# astable_555_timer.net
KiCad netlist of a schematic drawn in EAGLE
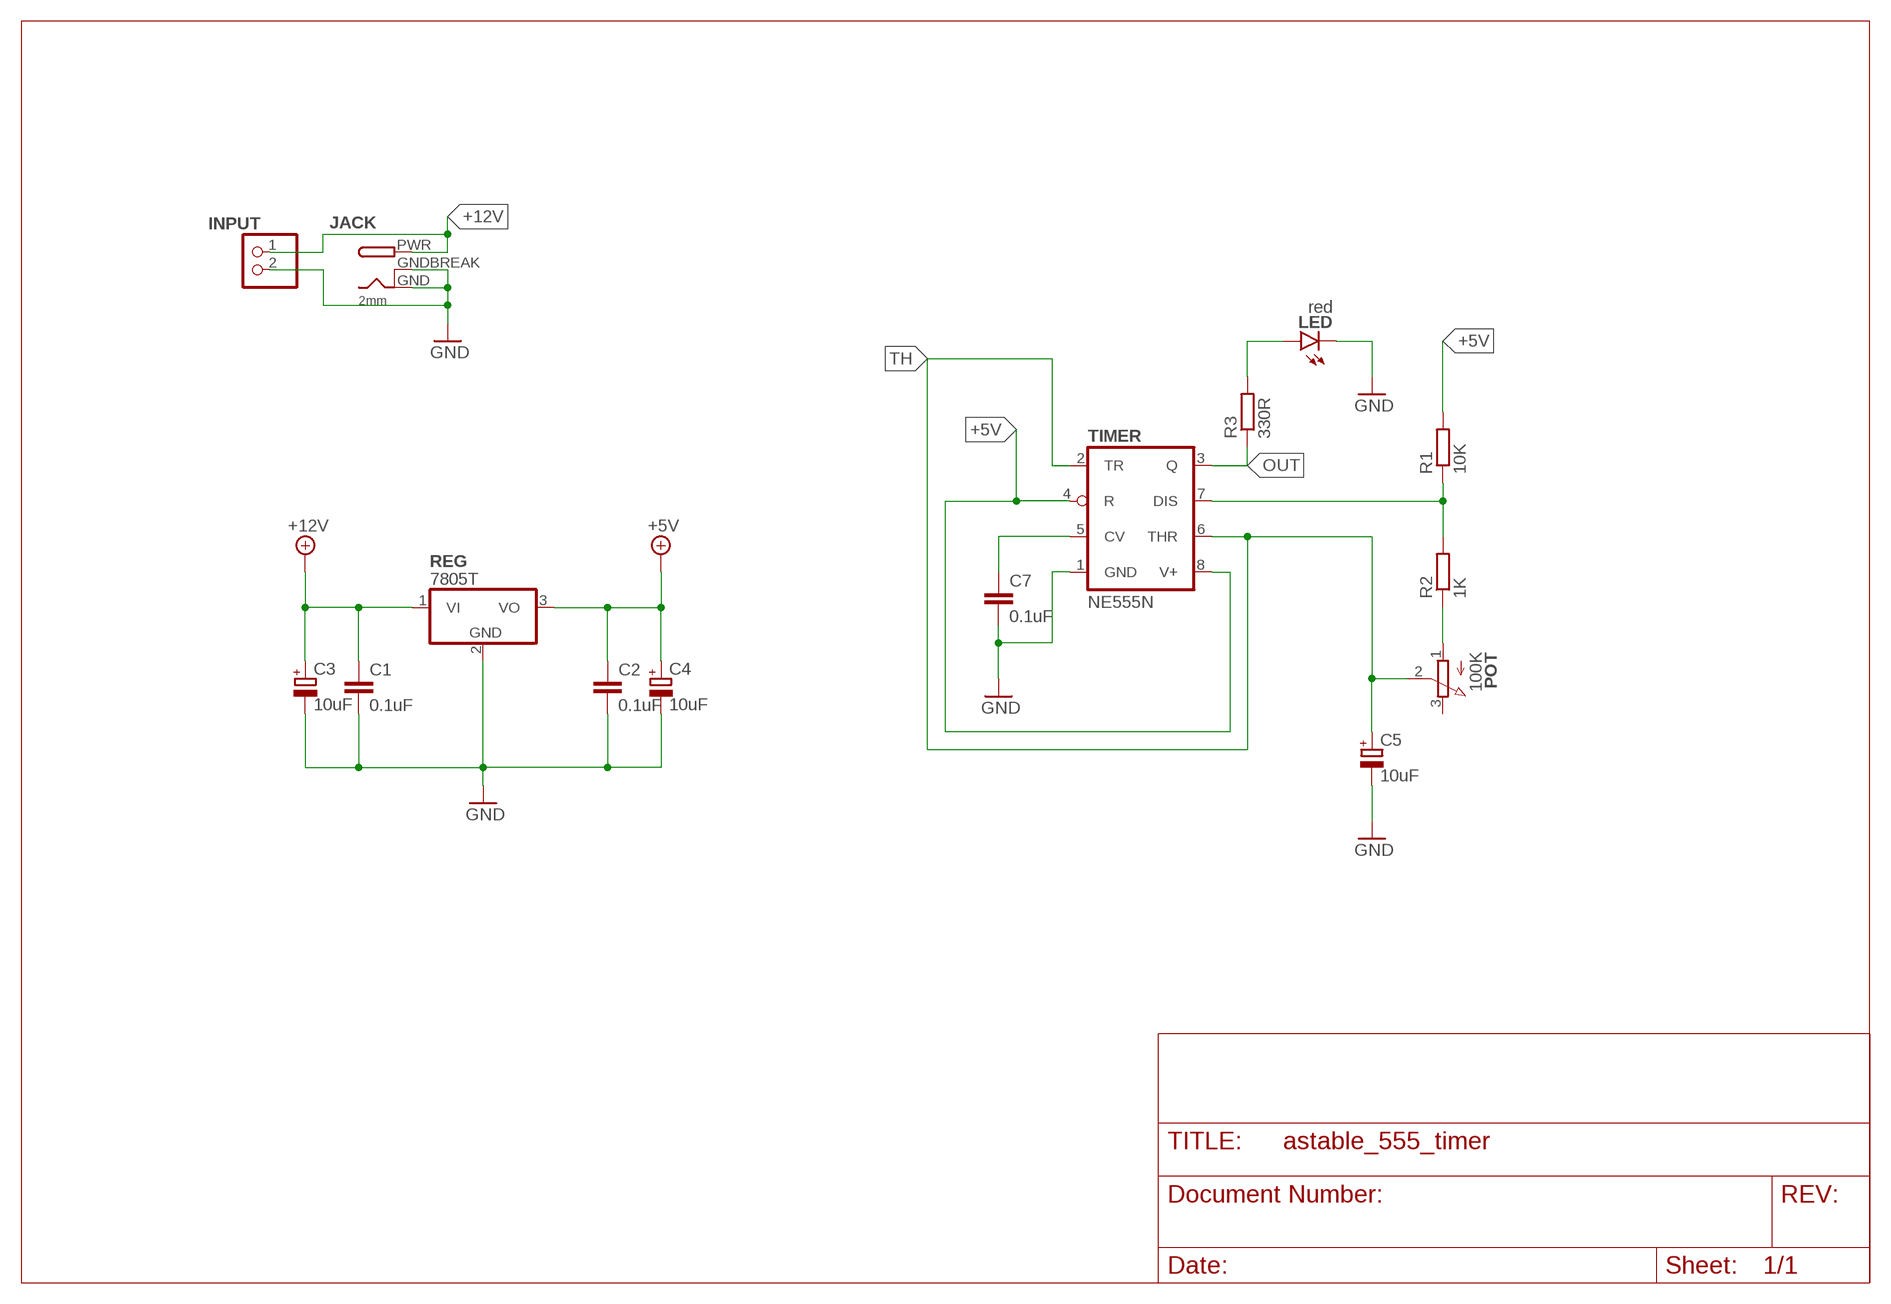
[diagram p0: schematic, sheet 1]

(export (version "E")
  (design (tool "Eeschema 10.0.6"))
  (components
    (comp (ref "C1")
      (value "0.1uF")
      (footprint "eagle-import:C050-030X075")
      (libsource (lib "eagle-import") (part "C-EU050-030X075"))
    )
    (comp (ref "C2")
      (value "0.1uF")
      (footprint "eagle-import:C050-030X075")
      (libsource (lib "eagle-import") (part "C-EU050-030X075"))
    )
    (comp (ref "C3")
      (value "10uF")
      (footprint "eagle-import:E3,5-8")
      (libsource (lib "eagle-import") (part "CPOL-EUE3.5-8"))
    )
    (comp (ref "C4")
      (value "10uF")
      (footprint "eagle-import:E3,5-8")
      (libsource (lib "eagle-import") (part "CPOL-EUE3.5-8"))
    )
    (comp (ref "C5")
      (value "10uF")
      (footprint "eagle-import:E3,5-8")
      (libsource (lib "eagle-import") (part "CPOL-EUE3.5-8"))
    )
    (comp (ref "C7")
      (value "0.1uF")
      (footprint "eagle-import:C050-030X075")
      (libsource (lib "eagle-import") (part "C-EU050-030X075"))
    )
    (comp (ref "INPUT")
      (value "PINHD-1X2")
      (footprint "eagle-import:1X02")
      (libsource (lib "eagle-import") (part "PINHD-1X2"))
    )
    (comp (ref "JACK")
      (value "2mm")
      (footprint "eagle-import:DCJACK_2MM_PTH")
      (libsource (lib "eagle-import") (part "DCBARRELPTH"))
    )
    (comp (ref "LED")
      (value "red")
      (footprint "eagle-import:LED5MM")
      (libsource (lib "eagle-import") (part "LED5MM"))
    )
    (comp (ref "POT")
      (value "100K")
      (footprint "eagle-import:3RP_1610N")
      (libsource (lib "eagle-import") (part "3RP/1610N"))
    )
    (comp (ref "R1")
      (value "10K")
      (footprint "eagle-import:0207_10")
      (libsource (lib "eagle-import") (part "R-EU_0207/10"))
    )
    (comp (ref "R2")
      (value "1K")
      (footprint "eagle-import:0207_10")
      (libsource (lib "eagle-import") (part "R-EU_0207/10"))
    )
    (comp (ref "R3")
      (value "330R")
      (footprint "eagle-import:0207_10")
      (libsource (lib "eagle-import") (part "R-EU_0207/10"))
    )
    (comp (ref "REG")
      (value "7805T")
      (footprint "eagle-import:TO220H")
      (libsource (lib "eagle-import") (part "78T05"))
    )
    (comp (ref "TIMER")
      (value "NE555N")
      (footprint "eagle-import:DIL08")
      (libsource (lib "eagle-import") (part "555NNE"))
    )
  )
  (nets
    (net (code "1") (name "+5V") (class "Default")
      (node (ref "C2") (pin "1") (pinfunction "1_1") (pintype "passive"))
      (node (ref "C4") (pin "+") (pinfunction "+_+") (pintype "passive"))
      (node (ref "R1") (pin "2") (pinfunction "2_2") (pintype "passive"))
      (node (ref "REG") (pin "3") (pinfunction "VO_3") (pintype "passive"))
      (node (ref "TIMER") (pin "4") (pinfunction "R_4") (pintype "input"))
      (node (ref "TIMER") (pin "8") (pinfunction "V+_8") (pintype "power_in"))
    )
    (net (code "2") (name "+12V") (class "Default")
      (node (ref "C1") (pin "1") (pinfunction "1_1") (pintype "passive"))
      (node (ref "C3") (pin "+") (pinfunction "+_+") (pintype "passive"))
      (node (ref "INPUT") (pin "1") (pinfunction "1_1") (pintype "passive"))
      (node (ref "JACK") (pin "PWR") (pinfunction "PWR_PWR") (pintype "power_in"))
      (node (ref "REG") (pin "1") (pinfunction "VI_1") (pintype "input"))
    )
    (net (code "3") (name "GND") (class "Default")
      (node (ref "C1") (pin "2") (pinfunction "2_2") (pintype "passive"))
      (node (ref "C2") (pin "2") (pinfunction "2_2") (pintype "passive"))
      (node (ref "C3") (pin "-") (pinfunction "-_-") (pintype "passive"))
      (node (ref "C4") (pin "-") (pinfunction "-_-") (pintype "passive"))
      (node (ref "C5") (pin "-") (pinfunction "-_-") (pintype "passive"))
      (node (ref "C7") (pin "2") (pinfunction "2_2") (pintype "passive"))
      (node (ref "INPUT") (pin "2") (pinfunction "2_2") (pintype "passive"))
      (node (ref "JACK") (pin "GND") (pinfunction "GND_GND") (pintype "power_in"))
      (node (ref "JACK") (pin "GNDBREAK") (pinfunction "GNDBREAK_GNDBREAK") (pintype "power_in"))
      (node (ref "LED") (pin "K") (pinfunction "C_K") (pintype "passive"))
      (node (ref "REG") (pin "2") (pinfunction "GND_2") (pintype "passive"))
      (node (ref "TIMER") (pin "1") (pinfunction "GND_1") (pintype "power_in"))
    )
    (net (code "4") (name "Net-(LED-PadA)") (class "Default")
      (node (ref "LED") (pin "A") (pinfunction "A_A") (pintype "passive"))
      (node (ref "R3") (pin "2") (pinfunction "2_2") (pintype "passive"))
    )
    (net (code "5") (name "Net-(POT-A)") (class "Default")
      (node (ref "POT") (pin "1") (pinfunction "A_1") (pintype "passive"))
      (node (ref "R2") (pin "1") (pinfunction "1_1") (pintype "passive"))
    )
    (net (code "6") (name "Net-(TIMER-CV)") (class "Default")
      (node (ref "C7") (pin "1") (pinfunction "1_1") (pintype "passive"))
      (node (ref "TIMER") (pin "5") (pinfunction "CV_5") (pintype "input"))
    )
    (net (code "7") (name "Net-(TIMER-DIS)") (class "Default")
      (node (ref "R1") (pin "1") (pinfunction "1_1") (pintype "passive"))
      (node (ref "R2") (pin "2") (pinfunction "2_2") (pintype "passive"))
      (node (ref "TIMER") (pin "7") (pinfunction "DIS_7") (pintype "input"))
    )
    (net (code "8") (name "OUT") (class "Default")
      (node (ref "R3") (pin "1") (pinfunction "1_1") (pintype "passive"))
      (node (ref "TIMER") (pin "3") (pinfunction "Q_3") (pintype "output"))
    )
    (net (code "9") (name "TH") (class "Default")
      (node (ref "C5") (pin "+") (pinfunction "+_+") (pintype "passive"))
      (node (ref "POT") (pin "2") (pinfunction "S_2") (pintype "passive"))
      (node (ref "TIMER") (pin "2") (pinfunction "TR_2") (pintype "input"))
      (node (ref "TIMER") (pin "6") (pinfunction "THR_6") (pintype "input"))
    )
    (net (code "10") (name "unconnected-(POT-E-Pad3)") (class "Default")
      (node (ref "POT") (pin "3") (pinfunction "E_3") (pintype "passive"))
    )
  )
)
